# airu-schematic.net
KiCad netlist of a schematic drawn in EAGLE
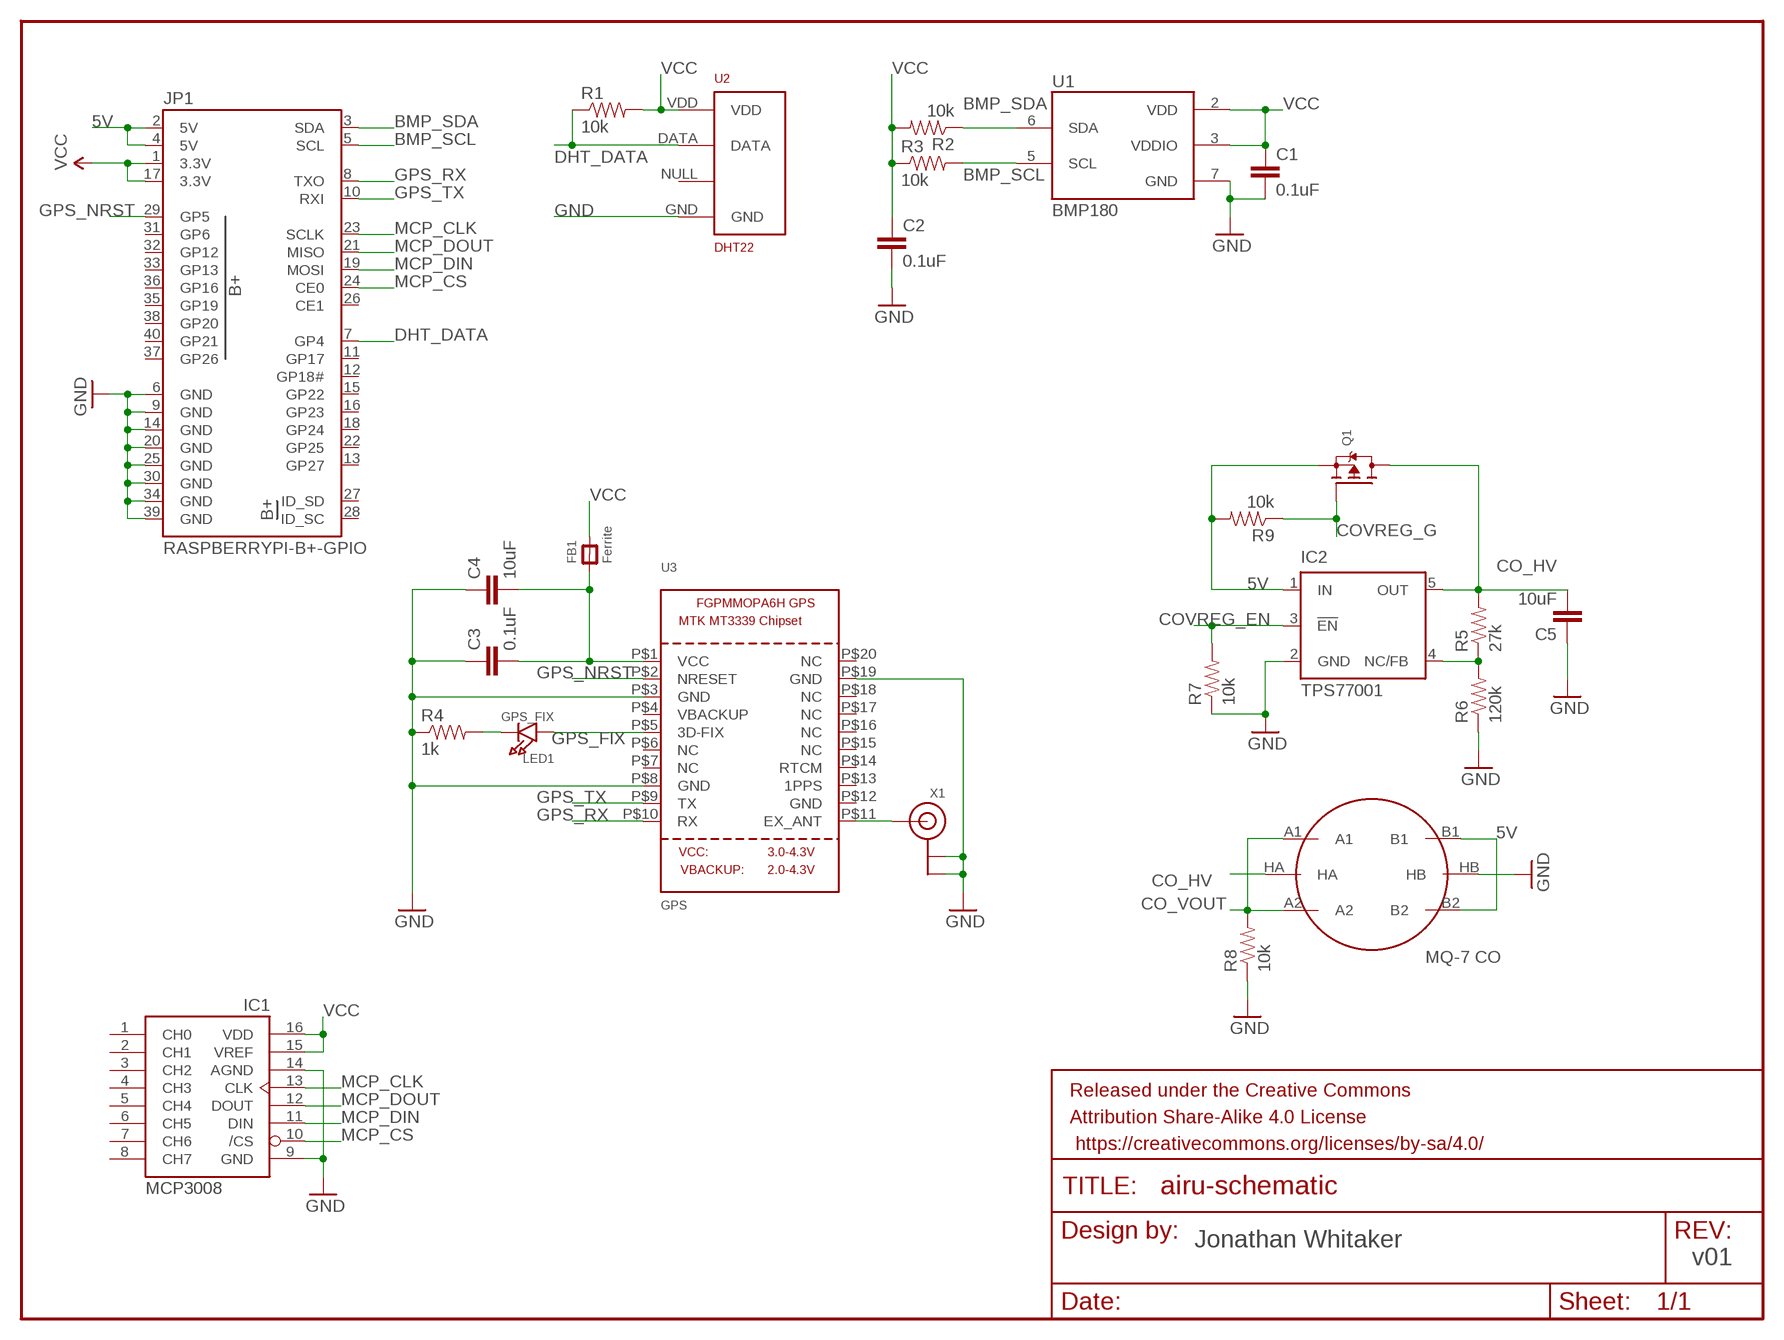
[diagram p0: schematic, sheet 1]

(export (version "E")
  (design (tool "Eeschema 10.0.6"))
  (components
    (comp (ref "C1")
      (value "0.1uF")
      (footprint "eagle-import:1206")
      (libsource (lib "eagle-import") (part "CAP1206"))
    )
    (comp (ref "C2")
      (value "0.1uF")
      (footprint "eagle-import:1206")
      (libsource (lib "eagle-import") (part "CAP1206"))
    )
    (comp (ref "C3")
      (value "0.1uF")
      (footprint "eagle-import:1206")
      (libsource (lib "eagle-import") (part "CAP1206"))
    )
    (comp (ref "C4")
      (value "10uF")
      (footprint "eagle-import:1206")
      (libsource (lib "eagle-import") (part "CAP1206"))
    )
    (comp (ref "C5")
      (value "10uF")
      (footprint "eagle-import:1206")
      (libsource (lib "eagle-import") (part "CAP1206"))
    )
    (comp (ref "FB1")
      (value "Ferrite")
      (footprint "eagle-import:0805")
      (libsource (lib "eagle-import") (part "FERRITE0805"))
    )
    (comp (ref "FRAME1")
      (value "FRAME-LETTER")
      (footprint "eagle-import:CREATIVE_COMMONS")
      (fields
        (field (name "DESIGNER") "Jonathan Whitaker")
        (field (name "VERSION") "v01")
        (field (name "DESIGNER_1") "Jonathan Whitaker")
      )
      (libsource (lib "eagle-import") (part "FRAME-LETTER"))
    )
    (comp (ref "IC1")
      (value "MCP3008")
      (footprint "eagle-import:DIL16")
      (libsource (lib "eagle-import") (part "MCP3008"))
    )
    (comp (ref "IC2")
      (value "TPS77001")
      (footprint "eagle-import:SOT23-DBV")
      (fields (field (name "MF") "TEXAS INSTRUMENTS") (field (name "MPN") "TPS77001DBVT"))
      (libsource (lib "eagle-import") (part "TPS77001"))
    )
    (comp (ref "JP1")
      (value "RASPBERRYPI-B+-GPIO")
      (footprint "eagle-import:2X20-SHROUDED")
      (libsource (lib "eagle-import") (part "RASPBERRYPI-B+-GPIO"))
    )
    (comp (ref "LED1")
      (value "GPS_FIX")
      (footprint "eagle-import:CHIPLED_1206")
      (libsource (lib "eagle-import") (part "LED1206"))
    )
    (comp (ref "Q1")
      (value "MOSFET-P")
      (footprint "eagle-import:SOT23-R")
      (libsource (lib "eagle-import") (part "MOSFET-P"))
    )
    (comp (ref "R1")
      (value "10k")
      (footprint "eagle-import:1206")
      (libsource (lib "eagle-import") (part "RESISTOR1206"))
    )
    (comp (ref "R2")
      (value "10k")
      (footprint "eagle-import:1206")
      (libsource (lib "eagle-import") (part "RESISTOR1206"))
    )
    (comp (ref "R3")
      (value "10k")
      (footprint "eagle-import:1206")
      (libsource (lib "eagle-import") (part "RESISTOR1206"))
    )
    (comp (ref "R4")
      (value "1k")
      (footprint "eagle-import:1206")
      (libsource (lib "eagle-import") (part "RESISTOR1206"))
    )
    (comp (ref "R5")
      (value "27k")
      (footprint "eagle-import:1206")
      (libsource (lib "eagle-import") (part "RESISTOR1206"))
    )
    (comp (ref "R6")
      (value "120k")
      (footprint "eagle-import:1206")
      (libsource (lib "eagle-import") (part "RESISTOR1206"))
    )
    (comp (ref "R7")
      (value "10k")
      (footprint "eagle-import:1206")
      (libsource (lib "eagle-import") (part "RESISTOR1206"))
    )
    (comp (ref "R8")
      (value "10k")
      (footprint "eagle-import:1206")
      (libsource (lib "eagle-import") (part "RESISTOR1206"))
    )
    (comp (ref "R9")
      (value "10k")
      (footprint "eagle-import:1206")
      (libsource (lib "eagle-import") (part "RESISTOR1206"))
    )
    (comp (ref "U$1")
      (value "METHANE_SENSOR")
      (footprint "eagle-import:MQ-3")
      (libsource (lib "eagle-import") (part "METHANE_SENSOR"))
    )
    (comp (ref "U1")
      (value "BMP180")
      (footprint "eagle-import:BMP180")
      (libsource (lib "eagle-import") (part "BMP180"))
    )
    (comp (ref "U2")
      (value "DHT22")
      (footprint "eagle-import:RHT03_DHT-22")
      (libsource (lib "eagle-import") (part "RHT03_DHT-22_AM2302"))
    )
    (comp (ref "U3")
      (value "GPS")
      (footprint "eagle-import:FGPMMOPA6H")
      (libsource (lib "eagle-import") (part "GPS_FGPMMOPA6H"))
    )
    (comp (ref "X1")
      (value "ANTENNA_U.FL")
      (footprint "eagle-import:U.FL")
      (libsource (lib "eagle-import") (part "ANTENNA_U.FL"))
    )
  )
  (nets
    (net (code "1") (name "/5V") (class "Default")
      (node (ref "IC2") (pin "1") (pinfunction "IN_1") (pintype "input"))
      (node (ref "JP1") (pin "2") (pinfunction "5V_2") (pintype "power_in"))
      (node (ref "JP1") (pin "4") (pinfunction "5V_4") (pintype "power_in"))
      (node (ref "Q1") (pin "2") (pinfunction "S_2") (pintype "passive"))
      (node (ref "R9") (pin "2") (pinfunction "2_2") (pintype "passive"))
      (node (ref "U$1") (pin "B1") (pinfunction "B1_B1") (pintype "bidirectional"))
      (node (ref "U$1") (pin "B2") (pinfunction "B2_B2") (pintype "bidirectional"))
    )
    (net (code "2") (name "/BMP_SCL") (class "Default")
      (node (ref "JP1") (pin "5") (pinfunction "SCL_5") (pintype "bidirectional"))
      (node (ref "R3") (pin "2") (pinfunction "2_2") (pintype "passive"))
      (node (ref "U1") (pin "5") (pinfunction "SCL_5") (pintype "input"))
    )
    (net (code "3") (name "/BMP_SDA") (class "Default")
      (node (ref "JP1") (pin "3") (pinfunction "SDA_3") (pintype "bidirectional"))
      (node (ref "R2") (pin "1") (pinfunction "1_1") (pintype "passive"))
      (node (ref "U1") (pin "6") (pinfunction "SDA_6") (pintype "bidirectional"))
    )
    (net (code "4") (name "/COVREG_EN") (class "Default")
      (node (ref "IC2") (pin "3") (pinfunction "~{EN}_3") (pintype "input"))
      (node (ref "R7") (pin "2") (pinfunction "2_2") (pintype "passive"))
    )
    (net (code "5") (name "/COVREG_G") (class "Default")
      (node (ref "Q1") (pin "1") (pinfunction "G_1") (pintype "passive"))
      (node (ref "R9") (pin "1") (pinfunction "1_1") (pintype "passive"))
    )
    (net (code "6") (name "/CO_HV") (class "Default")
      (node (ref "C5") (pin "2") (pinfunction "2_2") (pintype "passive"))
      (node (ref "IC2") (pin "5") (pinfunction "OUT_5") (pintype "passive"))
      (node (ref "Q1") (pin "3") (pinfunction "D_3") (pintype "passive"))
      (node (ref "R5") (pin "2") (pinfunction "2_2") (pintype "passive"))
      (node (ref "U$1") (pin "HA") (pinfunction "HA_HA") (pintype "bidirectional"))
    )
    (net (code "7") (name "/CO_VOUT") (class "Default")
      (node (ref "R8") (pin "2") (pinfunction "2_2") (pintype "passive"))
      (node (ref "U$1") (pin "A1") (pinfunction "A1_A1") (pintype "bidirectional"))
      (node (ref "U$1") (pin "A2") (pinfunction "A2_A2") (pintype "bidirectional"))
    )
    (net (code "8") (name "/DHT_DATA") (class "Default")
      (node (ref "JP1") (pin "7") (pinfunction "GP4_7") (pintype "bidirectional"))
      (node (ref "R1") (pin "1") (pinfunction "1_1") (pintype "passive"))
      (node (ref "U2") (pin "DATA") (pinfunction "DATA_DATA") (pintype "bidirectional"))
    )
    (net (code "9") (name "/GPS_FIX") (class "Default")
      (node (ref "LED1") (pin "A") (pinfunction "A_A") (pintype "passive"))
      (node (ref "U3") (pin "P$5") (pinfunction "3D-FIX_P$5") (pintype "bidirectional"))
    )
    (net (code "10") (name "/GPS_NRST") (class "Default")
      (node (ref "JP1") (pin "29") (pinfunction "GP5_29") (pintype "bidirectional"))
      (node (ref "U3") (pin "P$2") (pinfunction "NRESET_P$2") (pintype "bidirectional"))
    )
    (net (code "11") (name "/GPS_RX") (class "Default")
      (node (ref "JP1") (pin "8") (pinfunction "TXO_8") (pintype "output"))
      (node (ref "U3") (pin "P$10") (pinfunction "RX_P$10") (pintype "bidirectional"))
    )
    (net (code "12") (name "/GPS_TX") (class "Default")
      (node (ref "JP1") (pin "10") (pinfunction "RXI_10") (pintype "input"))
      (node (ref "U3") (pin "P$9") (pinfunction "TX_P$9") (pintype "bidirectional"))
    )
    (net (code "13") (name "/MCP_CLK") (class "Default")
      (node (ref "IC1") (pin "13") (pinfunction "CLK_13") (pintype "input"))
      (node (ref "JP1") (pin "23") (pinfunction "SCLK_23") (pintype "output"))
    )
    (net (code "14") (name "/MCP_CS") (class "Default")
      (node (ref "IC1") (pin "10") (pinfunction "/CS_10") (pintype "input"))
      (node (ref "JP1") (pin "24") (pinfunction "CE0_24") (pintype "output"))
    )
    (net (code "15") (name "/MCP_DIN") (class "Default")
      (node (ref "IC1") (pin "11") (pinfunction "DIN_11") (pintype "input"))
      (node (ref "JP1") (pin "19") (pinfunction "MOSI_19") (pintype "output"))
    )
    (net (code "16") (name "/MCP_DOUT") (class "Default")
      (node (ref "IC1") (pin "12") (pinfunction "DOUT_12") (pintype "output"))
      (node (ref "JP1") (pin "21") (pinfunction "MISO_21") (pintype "input"))
    )
    (net (code "17") (name "GND") (class "Default")
      (node (ref "C1") (pin "2") (pinfunction "2_2") (pintype "passive"))
      (node (ref "C2") (pin "2") (pinfunction "2_2") (pintype "passive"))
      (node (ref "C3") (pin "1") (pinfunction "1_1") (pintype "passive"))
      (node (ref "C4") (pin "1") (pinfunction "1_1") (pintype "passive"))
      (node (ref "C5") (pin "1") (pinfunction "1_1") (pintype "passive"))
      (node (ref "IC1") (pin "14") (pinfunction "AGND_14") (pintype "power_in"))
      (node (ref "IC1") (pin "9") (pinfunction "GND_9") (pintype "power_in"))
      (node (ref "IC2") (pin "2") (pinfunction "GND_2") (pintype "power_in"))
      (node (ref "JP1") (pin "14") (pinfunction "GND_14") (pintype "power_in"))
      (node (ref "JP1") (pin "20") (pinfunction "GND_20") (pintype "power_in"))
      (node (ref "JP1") (pin "25") (pinfunction "GND_25") (pintype "power_in"))
      (node (ref "JP1") (pin "30") (pinfunction "GND_30") (pintype "power_in"))
      (node (ref "JP1") (pin "34") (pinfunction "GND_34") (pintype "power_in"))
      (node (ref "JP1") (pin "39") (pinfunction "GND_39") (pintype "power_in"))
      (node (ref "JP1") (pin "6") (pinfunction "GND_6") (pintype "power_in"))
      (node (ref "JP1") (pin "9") (pinfunction "GND_9") (pintype "power_in"))
      (node (ref "R4") (pin "1") (pinfunction "1_1") (pintype "passive"))
      (node (ref "R6") (pin "1") (pinfunction "1_1") (pintype "passive"))
      (node (ref "R7") (pin "1") (pinfunction "1_1") (pintype "passive"))
      (node (ref "R8") (pin "1") (pinfunction "1_1") (pintype "passive"))
      (node (ref "U$1") (pin "HB") (pinfunction "HB_HB") (pintype "bidirectional"))
      (node (ref "U1") (pin "7") (pinfunction "GND_7") (pintype "power_in"))
      (node (ref "U2") (pin "GND") (pinfunction "GND_GND") (pintype "power_in"))
      (node (ref "U3") (pin "P$19") (pinfunction "GND_P$19") (pintype "bidirectional"))
      (node (ref "U3") (pin "P$3") (pinfunction "GND_P$3") (pintype "bidirectional"))
      (node (ref "U3") (pin "P$8") (pinfunction "GND_P$8") (pintype "bidirectional"))
      (node (ref "X1") (pin "1") (pinfunction "GND_1") (pintype "passive"))
      (node (ref "X1") (pin "2") (pinfunction "GND_2") (pintype "passive"))
    )
    (net (code "18") (name "Net-(FB1-P$1)") (class "Default")
      (node (ref "C3") (pin "2") (pinfunction "2_2") (pintype "passive"))
      (node (ref "C4") (pin "2") (pinfunction "2_2") (pintype "passive"))
      (node (ref "FB1") (pin "1") (pinfunction "P$1_1") (pintype "passive"))
      (node (ref "U3") (pin "P$1") (pinfunction "VCC_P$1") (pintype "bidirectional"))
    )
    (net (code "19") (name "Net-(IC2-NC{slash}FB)") (class "Default")
      (node (ref "IC2") (pin "4") (pinfunction "NC/FB_4") (pintype "passive"))
      (node (ref "R5") (pin "1") (pinfunction "1_1") (pintype "passive"))
      (node (ref "R6") (pin "2") (pinfunction "2_2") (pintype "passive"))
    )
    (net (code "20") (name "Net-(LED1-PadC)") (class "Default")
      (node (ref "LED1") (pin "C") (pinfunction "C_C") (pintype "passive"))
      (node (ref "R4") (pin "2") (pinfunction "2_2") (pintype "passive"))
    )
    (net (code "21") (name "Net-(U3-EX_ANT)") (class "Default")
      (node (ref "U3") (pin "P$11") (pinfunction "EX_ANT_P$11") (pintype "bidirectional"))
      (node (ref "X1") (pin "3") (pinfunction "SIGNAL_3") (pintype "passive"))
    )
    (net (code "22") (name "VCC") (class "Default")
      (node (ref "C1") (pin "1") (pinfunction "1_1") (pintype "passive"))
      (node (ref "C2") (pin "1") (pinfunction "1_1") (pintype "passive"))
      (node (ref "FB1") (pin "2") (pinfunction "P$2_2") (pintype "passive"))
      (node (ref "IC1") (pin "15") (pinfunction "VREF_15") (pintype "input"))
      (node (ref "IC1") (pin "16") (pinfunction "VDD_16") (pintype "power_in"))
      (node (ref "JP1") (pin "1") (pinfunction "3.3V_1") (pintype "power_in"))
      (node (ref "JP1") (pin "17") (pinfunction "3.3V_17") (pintype "power_in"))
      (node (ref "R1") (pin "2") (pinfunction "2_2") (pintype "passive"))
      (node (ref "R2") (pin "2") (pinfunction "2_2") (pintype "passive"))
      (node (ref "R3") (pin "1") (pinfunction "1_1") (pintype "passive"))
      (node (ref "U1") (pin "2") (pinfunction "VDD_2") (pintype "power_in"))
      (node (ref "U1") (pin "3") (pinfunction "VDDIO_3") (pintype "power_in"))
      (node (ref "U2") (pin "VDD") (pinfunction "VDD_VDD") (pintype "power_in"))
    )
    (net (code "23") (name "unconnected-(IC1-CH0-Pad1)") (class "Default")
      (node (ref "IC1") (pin "1") (pinfunction "CH0_1") (pintype "input"))
    )
    (net (code "24") (name "unconnected-(IC1-CH1-Pad2)") (class "Default")
      (node (ref "IC1") (pin "2") (pinfunction "CH1_2") (pintype "input"))
    )
    (net (code "25") (name "unconnected-(IC1-CH2-Pad3)") (class "Default")
      (node (ref "IC1") (pin "3") (pinfunction "CH2_3") (pintype "input"))
    )
    (net (code "26") (name "unconnected-(IC1-CH3-Pad4)") (class "Default")
      (node (ref "IC1") (pin "4") (pinfunction "CH3_4") (pintype "input"))
    )
    (net (code "27") (name "unconnected-(IC1-CH4-Pad5)") (class "Default")
      (node (ref "IC1") (pin "5") (pinfunction "CH4_5") (pintype "input"))
    )
    (net (code "28") (name "unconnected-(IC1-CH5-Pad6)") (class "Default")
      (node (ref "IC1") (pin "6") (pinfunction "CH5_6") (pintype "input"))
    )
    (net (code "29") (name "unconnected-(IC1-CH6-Pad7)") (class "Default")
      (node (ref "IC1") (pin "7") (pinfunction "CH6_7") (pintype "input"))
    )
    (net (code "30") (name "unconnected-(IC1-CH7-Pad8)") (class "Default")
      (node (ref "IC1") (pin "8") (pinfunction "CH7_8") (pintype "input"))
    )
    (net (code "31") (name "unconnected-(JP1-CE1-Pad26)") (class "Default")
      (node (ref "JP1") (pin "26") (pinfunction "CE1_26") (pintype "output"))
    )
    (net (code "32") (name "unconnected-(JP1-GP6-Pad31)") (class "Default")
      (node (ref "JP1") (pin "31") (pinfunction "GP6_31") (pintype "bidirectional"))
    )
    (net (code "33") (name "unconnected-(JP1-GP12-Pad32)") (class "Default")
      (node (ref "JP1") (pin "32") (pinfunction "GP12_32") (pintype "bidirectional"))
    )
    (net (code "34") (name "unconnected-(JP1-GP13-Pad33)") (class "Default")
      (node (ref "JP1") (pin "33") (pinfunction "GP13_33") (pintype "bidirectional"))
    )
    (net (code "35") (name "unconnected-(JP1-GP16-Pad36)") (class "Default")
      (node (ref "JP1") (pin "36") (pinfunction "GP16_36") (pintype "bidirectional"))
    )
    (net (code "36") (name "unconnected-(JP1-GP17-Pad11)") (class "Default")
      (node (ref "JP1") (pin "11") (pinfunction "GP17_11") (pintype "bidirectional"))
    )
    (net (code "37") (name "unconnected-(JP1-GP18#-Pad12)") (class "Default")
      (node (ref "JP1") (pin "12") (pinfunction "GP18#_12") (pintype "bidirectional"))
    )
    (net (code "38") (name "unconnected-(JP1-GP19-Pad35)") (class "Default")
      (node (ref "JP1") (pin "35") (pinfunction "GP19_35") (pintype "bidirectional"))
    )
    (net (code "39") (name "unconnected-(JP1-GP20-Pad38)") (class "Default")
      (node (ref "JP1") (pin "38") (pinfunction "GP20_38") (pintype "bidirectional"))
    )
    (net (code "40") (name "unconnected-(JP1-GP21-Pad40)") (class "Default")
      (node (ref "JP1") (pin "40") (pinfunction "GP21_40") (pintype "bidirectional"))
    )
    (net (code "41") (name "unconnected-(JP1-GP22-Pad15)") (class "Default")
      (node (ref "JP1") (pin "15") (pinfunction "GP22_15") (pintype "bidirectional"))
    )
    (net (code "42") (name "unconnected-(JP1-GP23-Pad16)") (class "Default")
      (node (ref "JP1") (pin "16") (pinfunction "GP23_16") (pintype "bidirectional"))
    )
    (net (code "43") (name "unconnected-(JP1-GP24-Pad18)") (class "Default")
      (node (ref "JP1") (pin "18") (pinfunction "GP24_18") (pintype "bidirectional"))
    )
    (net (code "44") (name "unconnected-(JP1-GP25-Pad22)") (class "Default")
      (node (ref "JP1") (pin "22") (pinfunction "GP25_22") (pintype "bidirectional"))
    )
    (net (code "45") (name "unconnected-(JP1-GP26-Pad37)") (class "Default")
      (node (ref "JP1") (pin "37") (pinfunction "GP26_37") (pintype "bidirectional"))
    )
    (net (code "46") (name "unconnected-(JP1-GP27-Pad13)") (class "Default")
      (node (ref "JP1") (pin "13") (pinfunction "GP27_13") (pintype "bidirectional"))
    )
    (net (code "47") (name "unconnected-(JP1-ID_SC-Pad28)") (class "Default")
      (node (ref "JP1") (pin "28") (pinfunction "ID_SC_28") (pintype "bidirectional"))
    )
    (net (code "48") (name "unconnected-(JP1-ID_SD-Pad27)") (class "Default")
      (node (ref "JP1") (pin "27") (pinfunction "ID_SD_27") (pintype "bidirectional"))
    )
    (net (code "49") (name "unconnected-(U2-PadNULL)") (class "Default")
      (node (ref "U2") (pin "NULL") (pinfunction "NULL_NULL") (pintype "no_connect"))
    )
    (net (code "50") (name "unconnected-(U3-1PPS-PadP$13)") (class "Default")
      (node (ref "U3") (pin "P$13") (pinfunction "1PPS_P$13") (pintype "bidirectional"))
    )
    (net (code "51") (name "unconnected-(U3-GND-PadP$12)") (class "Default")
      (node (ref "U3") (pin "P$12") (pinfunction "GND_P$12") (pintype "bidirectional"))
    )
    (net (code "52") (name "unconnected-(U3-NC-PadP$6)") (class "Default")
      (node (ref "U3") (pin "P$6") (pinfunction "NC_P$6") (pintype "bidirectional"))
    )
    (net (code "53") (name "unconnected-(U3-NC-PadP$7)") (class "Default")
      (node (ref "U3") (pin "P$7") (pinfunction "NC_P$7") (pintype "bidirectional"))
    )
    (net (code "54") (name "unconnected-(U3-NC-PadP$15)") (class "Default")
      (node (ref "U3") (pin "P$15") (pinfunction "NC_P$15") (pintype "bidirectional"))
    )
    (net (code "55") (name "unconnected-(U3-NC-PadP$16)") (class "Default")
      (node (ref "U3") (pin "P$16") (pinfunction "NC_P$16") (pintype "bidirectional"))
    )
    (net (code "56") (name "unconnected-(U3-NC-PadP$17)") (class "Default")
      (node (ref "U3") (pin "P$17") (pinfunction "NC_P$17") (pintype "bidirectional"))
    )
    (net (code "57") (name "unconnected-(U3-NC-PadP$18)") (class "Default")
      (node (ref "U3") (pin "P$18") (pinfunction "NC_P$18") (pintype "bidirectional"))
    )
    (net (code "58") (name "unconnected-(U3-NC-PadP$20)") (class "Default")
      (node (ref "U3") (pin "P$20") (pinfunction "NC_P$20") (pintype "bidirectional"))
    )
    (net (code "59") (name "unconnected-(U3-RTCM-PadP$14)") (class "Default")
      (node (ref "U3") (pin "P$14") (pinfunction "RTCM_P$14") (pintype "bidirectional"))
    )
    (net (code "60") (name "unconnected-(U3-VBACKUP-PadP$4)") (class "Default")
      (node (ref "U3") (pin "P$4") (pinfunction "VBACKUP_P$4") (pintype "bidirectional"))
    )
  )
)
